# servo.net
KiCad netlist of a schematic drawn in EAGLE
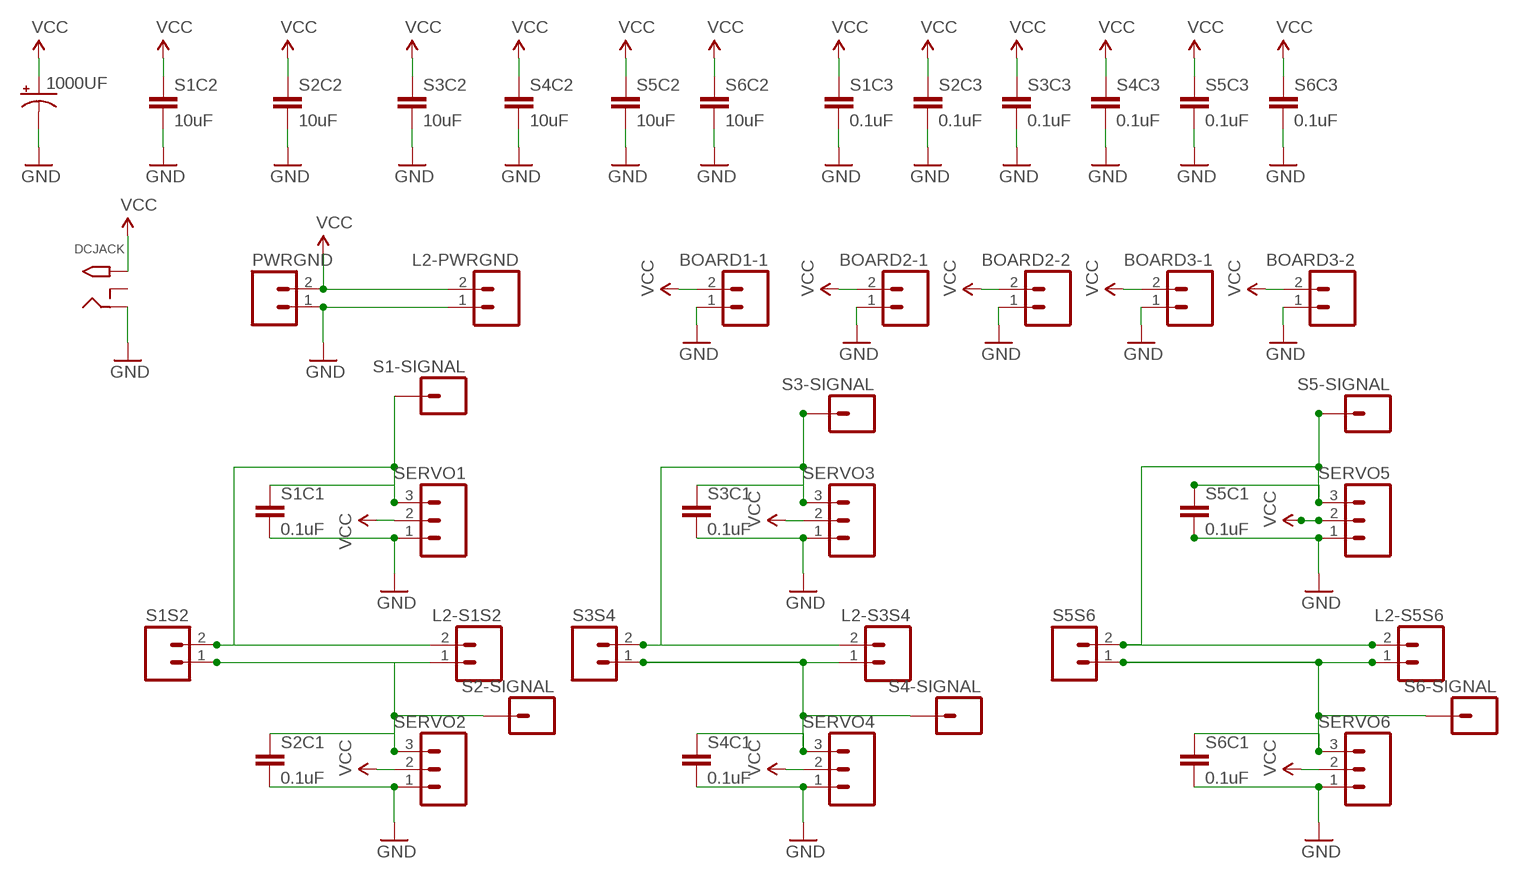
[diagram p0: schematic, sheet 1]

(export (version "E")
  (design (tool "Eeschema 10.0.6"))
  (components
    (comp (ref "1000UF")
      (value "CAP_POLG")
      (footprint "eagle-import:PANASONIC_G")
      (libsource (lib "eagle-import") (part "CAP_POLG"))
    )
    (comp (ref "BOARD1-1")
      (value "M02PTH")
      (footprint "eagle-import:1X02")
      (libsource (lib "eagle-import") (part "M02PTH"))
    )
    (comp (ref "BOARD2-1")
      (value "M02PTH")
      (footprint "eagle-import:1X02")
      (libsource (lib "eagle-import") (part "M02PTH"))
    )
    (comp (ref "BOARD2-2")
      (value "M02PTH")
      (footprint "eagle-import:1X02")
      (libsource (lib "eagle-import") (part "M02PTH"))
    )
    (comp (ref "BOARD3-1")
      (value "M02PTH")
      (footprint "eagle-import:1X02")
      (libsource (lib "eagle-import") (part "M02PTH"))
    )
    (comp (ref "BOARD3-2")
      (value "M02PTH")
      (footprint "eagle-import:1X02")
      (libsource (lib "eagle-import") (part "M02PTH"))
    )
    (comp (ref "DCJACK")
      (value "2.1MMJACKTHM")
      (footprint "eagle-import:PJ-102A")
      (libsource (lib "eagle-import") (part "2.1MMJACKTHM"))
    )
    (comp (ref "L2-PWRGND")
      (value "M02PTH")
      (footprint "eagle-import:1X02")
      (libsource (lib "eagle-import") (part "M02PTH"))
    )
    (comp (ref "L2-S1S2")
      (value "M02PTH")
      (footprint "eagle-import:1X02")
      (libsource (lib "eagle-import") (part "M02PTH"))
    )
    (comp (ref "L2-S3S4")
      (value "M02PTH")
      (footprint "eagle-import:1X02")
      (libsource (lib "eagle-import") (part "M02PTH"))
    )
    (comp (ref "L2-S5S6")
      (value "M02PTH")
      (footprint "eagle-import:1X02")
      (libsource (lib "eagle-import") (part "M02PTH"))
    )
    (comp (ref "PWRGND")
      (value "M02PTH")
      (footprint "eagle-import:1X02")
      (libsource (lib "eagle-import") (part "M02PTH"))
    )
    (comp (ref "S1-SIGNAL")
      (value "M01PTH")
      (footprint "eagle-import:1X01")
      (libsource (lib "eagle-import") (part "M01PTH"))
    )
    (comp (ref "S1C1")
      (value "0.1uF")
      (footprint "eagle-import:0603-CAP")
      (libsource (lib "eagle-import") (part "0.1UF-25V-5%(0603)"))
    )
    (comp (ref "S1C2")
      (value "10uF")
      (footprint "eagle-import:0603-CAP")
      (libsource (lib "eagle-import") (part "10UF-6.3V-20%(0603)"))
    )
    (comp (ref "S1C3")
      (value "0.1uF")
      (footprint "eagle-import:0603-CAP")
      (libsource (lib "eagle-import") (part "0.1UF-25V-5%(0603)"))
    )
    (comp (ref "S1S2")
      (value "M02PTH")
      (footprint "eagle-import:1X02")
      (libsource (lib "eagle-import") (part "M02PTH"))
    )
    (comp (ref "S2-SIGNAL")
      (value "M01PTH")
      (footprint "eagle-import:1X01")
      (libsource (lib "eagle-import") (part "M01PTH"))
    )
    (comp (ref "S2C1")
      (value "0.1uF")
      (footprint "eagle-import:0603-CAP")
      (libsource (lib "eagle-import") (part "0.1UF-25V-5%(0603)"))
    )
    (comp (ref "S2C2")
      (value "10uF")
      (footprint "eagle-import:0603-CAP")
      (libsource (lib "eagle-import") (part "10UF-6.3V-20%(0603)"))
    )
    (comp (ref "S2C3")
      (value "0.1uF")
      (footprint "eagle-import:0603-CAP")
      (libsource (lib "eagle-import") (part "0.1UF-25V-5%(0603)"))
    )
    (comp (ref "S3-SIGNAL")
      (value "M01PTH")
      (footprint "eagle-import:1X01")
      (libsource (lib "eagle-import") (part "M01PTH"))
    )
    (comp (ref "S3C1")
      (value "0.1uF")
      (footprint "eagle-import:0603-CAP")
      (libsource (lib "eagle-import") (part "0.1UF-25V-5%(0603)"))
    )
    (comp (ref "S3C2")
      (value "10uF")
      (footprint "eagle-import:0603-CAP")
      (libsource (lib "eagle-import") (part "10UF-6.3V-20%(0603)"))
    )
    (comp (ref "S3C3")
      (value "0.1uF")
      (footprint "eagle-import:0603-CAP")
      (libsource (lib "eagle-import") (part "0.1UF-25V-5%(0603)"))
    )
    (comp (ref "S3S4")
      (value "M02PTH")
      (footprint "eagle-import:1X02")
      (libsource (lib "eagle-import") (part "M02PTH"))
    )
    (comp (ref "S4-SIGNAL")
      (value "M01PTH")
      (footprint "eagle-import:1X01")
      (libsource (lib "eagle-import") (part "M01PTH"))
    )
    (comp (ref "S4C1")
      (value "0.1uF")
      (footprint "eagle-import:0603-CAP")
      (libsource (lib "eagle-import") (part "0.1UF-25V-5%(0603)"))
    )
    (comp (ref "S4C2")
      (value "10uF")
      (footprint "eagle-import:0603-CAP")
      (libsource (lib "eagle-import") (part "10UF-6.3V-20%(0603)"))
    )
    (comp (ref "S4C3")
      (value "0.1uF")
      (footprint "eagle-import:0603-CAP")
      (libsource (lib "eagle-import") (part "0.1UF-25V-5%(0603)"))
    )
    (comp (ref "S5-SIGNAL")
      (value "M01PTH")
      (footprint "eagle-import:1X01")
      (libsource (lib "eagle-import") (part "M01PTH"))
    )
    (comp (ref "S5C1")
      (value "0.1uF")
      (footprint "eagle-import:0603-CAP")
      (libsource (lib "eagle-import") (part "0.1UF-25V-5%(0603)"))
    )
    (comp (ref "S5C2")
      (value "10uF")
      (footprint "eagle-import:0603-CAP")
      (libsource (lib "eagle-import") (part "10UF-6.3V-20%(0603)"))
    )
    (comp (ref "S5C3")
      (value "0.1uF")
      (footprint "eagle-import:0603-CAP")
      (libsource (lib "eagle-import") (part "0.1UF-25V-5%(0603)"))
    )
    (comp (ref "S5S6")
      (value "M02PTH")
      (footprint "eagle-import:1X02")
      (libsource (lib "eagle-import") (part "M02PTH"))
    )
    (comp (ref "S6-SIGNAL")
      (value "M01PTH")
      (footprint "eagle-import:1X01")
      (libsource (lib "eagle-import") (part "M01PTH"))
    )
    (comp (ref "S6C1")
      (value "0.1uF")
      (footprint "eagle-import:0603-CAP")
      (libsource (lib "eagle-import") (part "0.1UF-25V-5%(0603)"))
    )
    (comp (ref "S6C2")
      (value "10uF")
      (footprint "eagle-import:0603-CAP")
      (libsource (lib "eagle-import") (part "10UF-6.3V-20%(0603)"))
    )
    (comp (ref "S6C3")
      (value "0.1uF")
      (footprint "eagle-import:0603-CAP")
      (libsource (lib "eagle-import") (part "0.1UF-25V-5%(0603)"))
    )
    (comp (ref "SERVO1")
      (value "M03PTH")
      (footprint "eagle-import:1X03")
      (libsource (lib "eagle-import") (part "M03PTH"))
    )
    (comp (ref "SERVO2")
      (value "M03PTH")
      (footprint "eagle-import:1X03")
      (libsource (lib "eagle-import") (part "M03PTH"))
    )
    (comp (ref "SERVO3")
      (value "M03PTH")
      (footprint "eagle-import:1X03")
      (libsource (lib "eagle-import") (part "M03PTH"))
    )
    (comp (ref "SERVO4")
      (value "M03PTH")
      (footprint "eagle-import:1X03")
      (libsource (lib "eagle-import") (part "M03PTH"))
    )
    (comp (ref "SERVO5")
      (value "M03PTH")
      (footprint "eagle-import:1X03")
      (libsource (lib "eagle-import") (part "M03PTH"))
    )
    (comp (ref "SERVO6")
      (value "M03PTH")
      (footprint "eagle-import:1X03")
      (libsource (lib "eagle-import") (part "M03PTH"))
    )
  )
  (nets
    (net (code "1") (name "GND") (class "Default")
      (node (ref "1000UF") (pin "-") (pinfunction "-_-") (pintype "passive"))
      (node (ref "BOARD1-1") (pin "1") (pinfunction "1_1") (pintype "passive"))
      (node (ref "BOARD2-1") (pin "1") (pinfunction "1_1") (pintype "passive"))
      (node (ref "BOARD2-2") (pin "1") (pinfunction "1_1") (pintype "passive"))
      (node (ref "BOARD3-1") (pin "1") (pinfunction "1_1") (pintype "passive"))
      (node (ref "BOARD3-2") (pin "1") (pinfunction "1_1") (pintype "passive"))
      (node (ref "DCJACK") (pin "RING") (pinfunction "RING_RING") (pintype "bidirectional"))
      (node (ref "L2-PWRGND") (pin "1") (pinfunction "1_1") (pintype "passive"))
      (node (ref "PWRGND") (pin "1") (pinfunction "1_1") (pintype "passive"))
      (node (ref "S1C1") (pin "2") (pinfunction "2_2") (pintype "passive"))
      (node (ref "S1C2") (pin "2") (pinfunction "2_2") (pintype "passive"))
      (node (ref "S1C3") (pin "2") (pinfunction "2_2") (pintype "passive"))
      (node (ref "S2C1") (pin "2") (pinfunction "2_2") (pintype "passive"))
      (node (ref "S2C2") (pin "2") (pinfunction "2_2") (pintype "passive"))
      (node (ref "S2C3") (pin "2") (pinfunction "2_2") (pintype "passive"))
      (node (ref "S3C1") (pin "2") (pinfunction "2_2") (pintype "passive"))
      (node (ref "S3C2") (pin "2") (pinfunction "2_2") (pintype "passive"))
      (node (ref "S3C3") (pin "2") (pinfunction "2_2") (pintype "passive"))
      (node (ref "S4C1") (pin "2") (pinfunction "2_2") (pintype "passive"))
      (node (ref "S4C2") (pin "2") (pinfunction "2_2") (pintype "passive"))
      (node (ref "S4C3") (pin "2") (pinfunction "2_2") (pintype "passive"))
      (node (ref "S5C1") (pin "2") (pinfunction "2_2") (pintype "passive"))
      (node (ref "S5C2") (pin "2") (pinfunction "2_2") (pintype "passive"))
      (node (ref "S5C3") (pin "2") (pinfunction "2_2") (pintype "passive"))
      (node (ref "S6C1") (pin "2") (pinfunction "2_2") (pintype "passive"))
      (node (ref "S6C2") (pin "2") (pinfunction "2_2") (pintype "passive"))
      (node (ref "S6C3") (pin "2") (pinfunction "2_2") (pintype "passive"))
      (node (ref "SERVO1") (pin "1") (pinfunction "1_1") (pintype "passive"))
      (node (ref "SERVO2") (pin "1") (pinfunction "1_1") (pintype "passive"))
      (node (ref "SERVO3") (pin "1") (pinfunction "1_1") (pintype "passive"))
      (node (ref "SERVO4") (pin "1") (pinfunction "1_1") (pintype "passive"))
      (node (ref "SERVO5") (pin "1") (pinfunction "1_1") (pintype "passive"))
      (node (ref "SERVO6") (pin "1") (pinfunction "1_1") (pintype "passive"))
    )
    (net (code "2") (name "Net-(L2-S1S2-Pad1)") (class "Default")
      (node (ref "L2-S1S2") (pin "1") (pinfunction "1_1") (pintype "passive"))
      (node (ref "S1S2") (pin "1") (pinfunction "1_1") (pintype "passive"))
      (node (ref "S2-SIGNAL") (pin "1") (pinfunction "1_1") (pintype "passive"))
      (node (ref "S2C1") (pin "1") (pinfunction "1_1") (pintype "passive"))
      (node (ref "SERVO2") (pin "3") (pinfunction "3_3") (pintype "passive"))
    )
    (net (code "3") (name "Net-(L2-S1S2-Pad2)") (class "Default")
      (node (ref "L2-S1S2") (pin "2") (pinfunction "2_2") (pintype "passive"))
      (node (ref "S1-SIGNAL") (pin "1") (pinfunction "1_1") (pintype "passive"))
      (node (ref "S1C1") (pin "1") (pinfunction "1_1") (pintype "passive"))
      (node (ref "S1S2") (pin "2") (pinfunction "2_2") (pintype "passive"))
      (node (ref "SERVO1") (pin "3") (pinfunction "3_3") (pintype "passive"))
    )
    (net (code "4") (name "Net-(L2-S3S4-Pad1)") (class "Default")
      (node (ref "L2-S3S4") (pin "1") (pinfunction "1_1") (pintype "passive"))
      (node (ref "S3S4") (pin "1") (pinfunction "1_1") (pintype "passive"))
      (node (ref "S4-SIGNAL") (pin "1") (pinfunction "1_1") (pintype "passive"))
      (node (ref "S4C1") (pin "1") (pinfunction "1_1") (pintype "passive"))
      (node (ref "SERVO4") (pin "3") (pinfunction "3_3") (pintype "passive"))
    )
    (net (code "5") (name "Net-(L2-S3S4-Pad2)") (class "Default")
      (node (ref "L2-S3S4") (pin "2") (pinfunction "2_2") (pintype "passive"))
      (node (ref "S3-SIGNAL") (pin "1") (pinfunction "1_1") (pintype "passive"))
      (node (ref "S3C1") (pin "1") (pinfunction "1_1") (pintype "passive"))
      (node (ref "S3S4") (pin "2") (pinfunction "2_2") (pintype "passive"))
      (node (ref "SERVO3") (pin "3") (pinfunction "3_3") (pintype "passive"))
    )
    (net (code "6") (name "Net-(L2-S5S6-Pad1)") (class "Default")
      (node (ref "L2-S5S6") (pin "1") (pinfunction "1_1") (pintype "passive"))
      (node (ref "S5S6") (pin "1") (pinfunction "1_1") (pintype "passive"))
      (node (ref "S6-SIGNAL") (pin "1") (pinfunction "1_1") (pintype "passive"))
      (node (ref "S6C1") (pin "1") (pinfunction "1_1") (pintype "passive"))
      (node (ref "SERVO6") (pin "3") (pinfunction "3_3") (pintype "passive"))
    )
    (net (code "7") (name "Net-(L2-S5S6-Pad2)") (class "Default")
      (node (ref "L2-S5S6") (pin "2") (pinfunction "2_2") (pintype "passive"))
      (node (ref "S5-SIGNAL") (pin "1") (pinfunction "1_1") (pintype "passive"))
      (node (ref "S5C1") (pin "1") (pinfunction "1_1") (pintype "passive"))
      (node (ref "S5S6") (pin "2") (pinfunction "2_2") (pintype "passive"))
      (node (ref "SERVO5") (pin "3") (pinfunction "3_3") (pintype "passive"))
    )
    (net (code "8") (name "VCC") (class "Default")
      (node (ref "1000UF") (pin "+") (pinfunction "+_+") (pintype "passive"))
      (node (ref "BOARD1-1") (pin "2") (pinfunction "2_2") (pintype "passive"))
      (node (ref "BOARD2-1") (pin "2") (pinfunction "2_2") (pintype "passive"))
      (node (ref "BOARD2-2") (pin "2") (pinfunction "2_2") (pintype "passive"))
      (node (ref "BOARD3-1") (pin "2") (pinfunction "2_2") (pintype "passive"))
      (node (ref "BOARD3-2") (pin "2") (pinfunction "2_2") (pintype "passive"))
      (node (ref "DCJACK") (pin "TIP") (pinfunction "TIP_TIP") (pintype "bidirectional"))
      (node (ref "L2-PWRGND") (pin "2") (pinfunction "2_2") (pintype "passive"))
      (node (ref "PWRGND") (pin "2") (pinfunction "2_2") (pintype "passive"))
      (node (ref "S1C2") (pin "1") (pinfunction "1_1") (pintype "passive"))
      (node (ref "S1C3") (pin "1") (pinfunction "1_1") (pintype "passive"))
      (node (ref "S2C2") (pin "1") (pinfunction "1_1") (pintype "passive"))
      (node (ref "S2C3") (pin "1") (pinfunction "1_1") (pintype "passive"))
      (node (ref "S3C2") (pin "1") (pinfunction "1_1") (pintype "passive"))
      (node (ref "S3C3") (pin "1") (pinfunction "1_1") (pintype "passive"))
      (node (ref "S4C2") (pin "1") (pinfunction "1_1") (pintype "passive"))
      (node (ref "S4C3") (pin "1") (pinfunction "1_1") (pintype "passive"))
      (node (ref "S5C2") (pin "1") (pinfunction "1_1") (pintype "passive"))
      (node (ref "S5C3") (pin "1") (pinfunction "1_1") (pintype "passive"))
      (node (ref "S6C2") (pin "1") (pinfunction "1_1") (pintype "passive"))
      (node (ref "S6C3") (pin "1") (pinfunction "1_1") (pintype "passive"))
      (node (ref "SERVO1") (pin "2") (pinfunction "2_2") (pintype "passive"))
      (node (ref "SERVO2") (pin "2") (pinfunction "2_2") (pintype "passive"))
      (node (ref "SERVO3") (pin "2") (pinfunction "2_2") (pintype "passive"))
      (node (ref "SERVO4") (pin "2") (pinfunction "2_2") (pintype "passive"))
      (node (ref "SERVO5") (pin "2") (pinfunction "2_2") (pintype "passive"))
      (node (ref "SERVO6") (pin "2") (pinfunction "2_2") (pintype "passive"))
    )
    (net (code "9") (name "unconnected-(DCJACK-PadRING_SW)") (class "Default")
      (node (ref "DCJACK") (pin "RING_SW") (pinfunction "RING_SW_RING_SW") (pintype "bidirectional"))
    )
  )
)
